# PCB-TLY-BRD-U.net
KiCad netlist of a schematic drawn in EAGLE
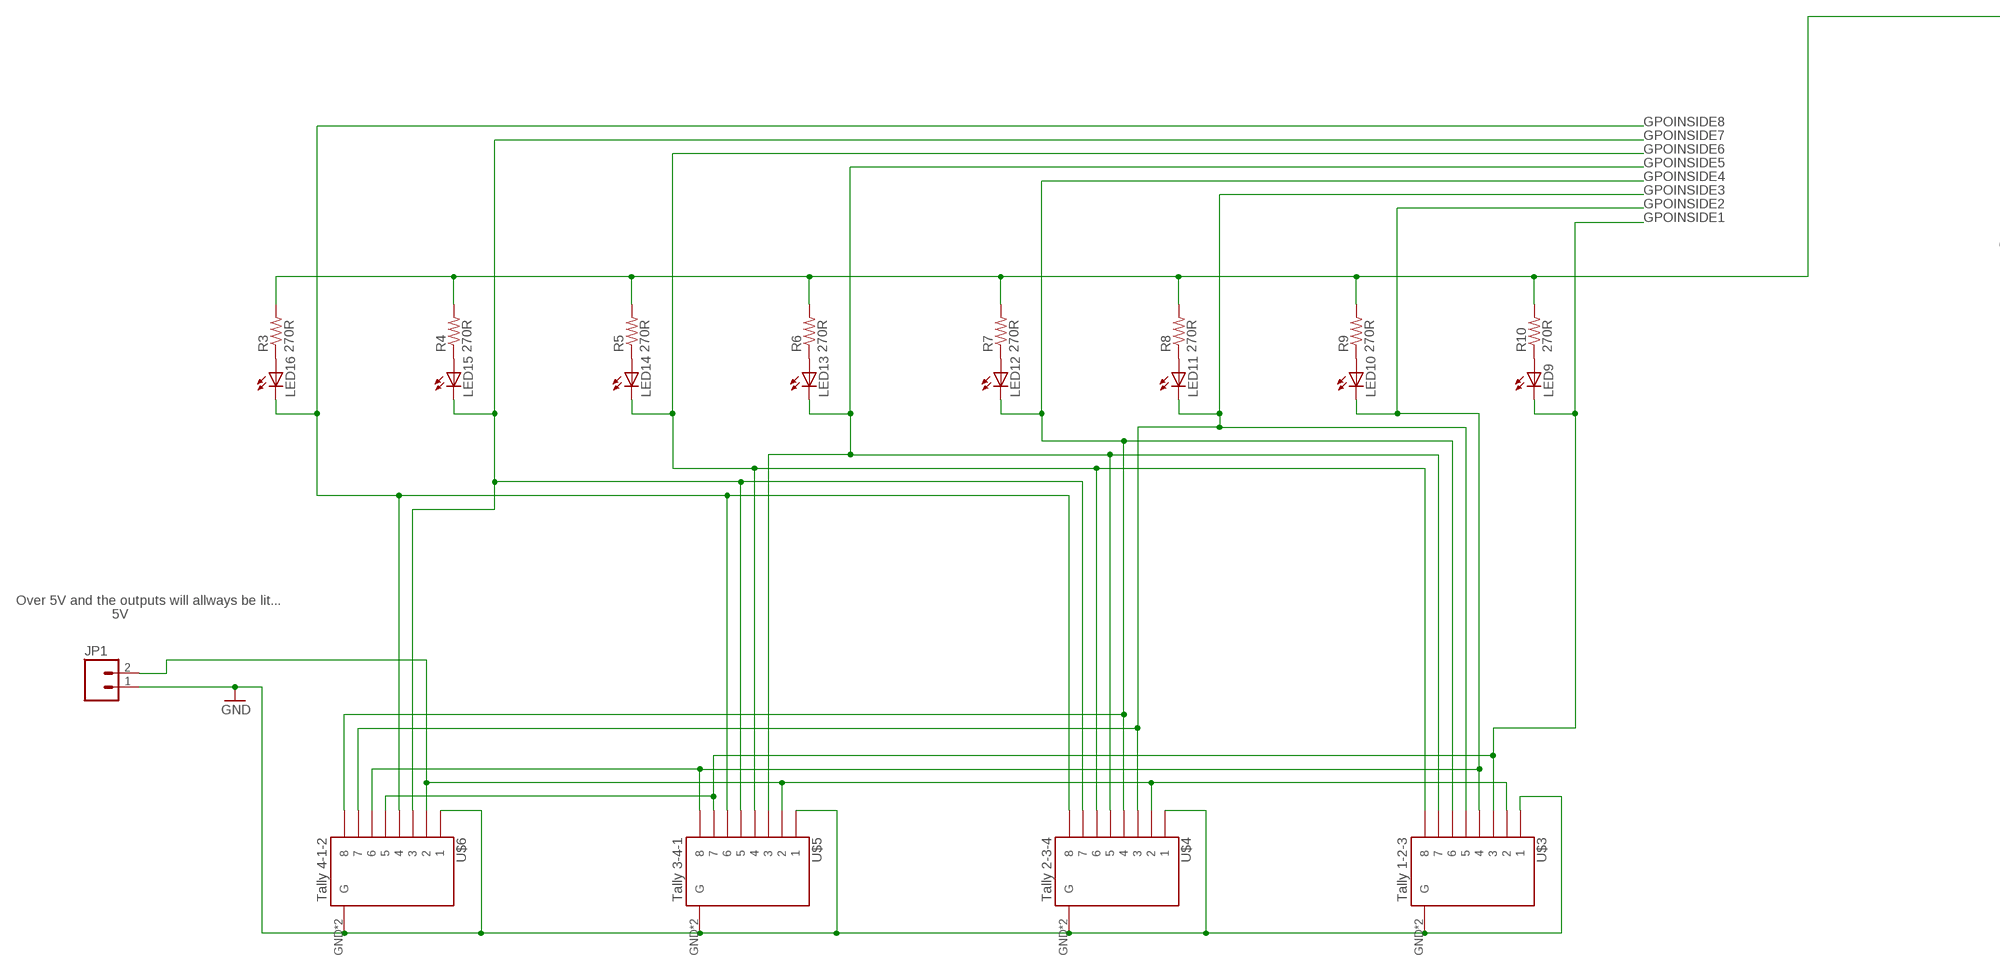
[diagram p0: schematic, sheet 1, part 1 of 2]
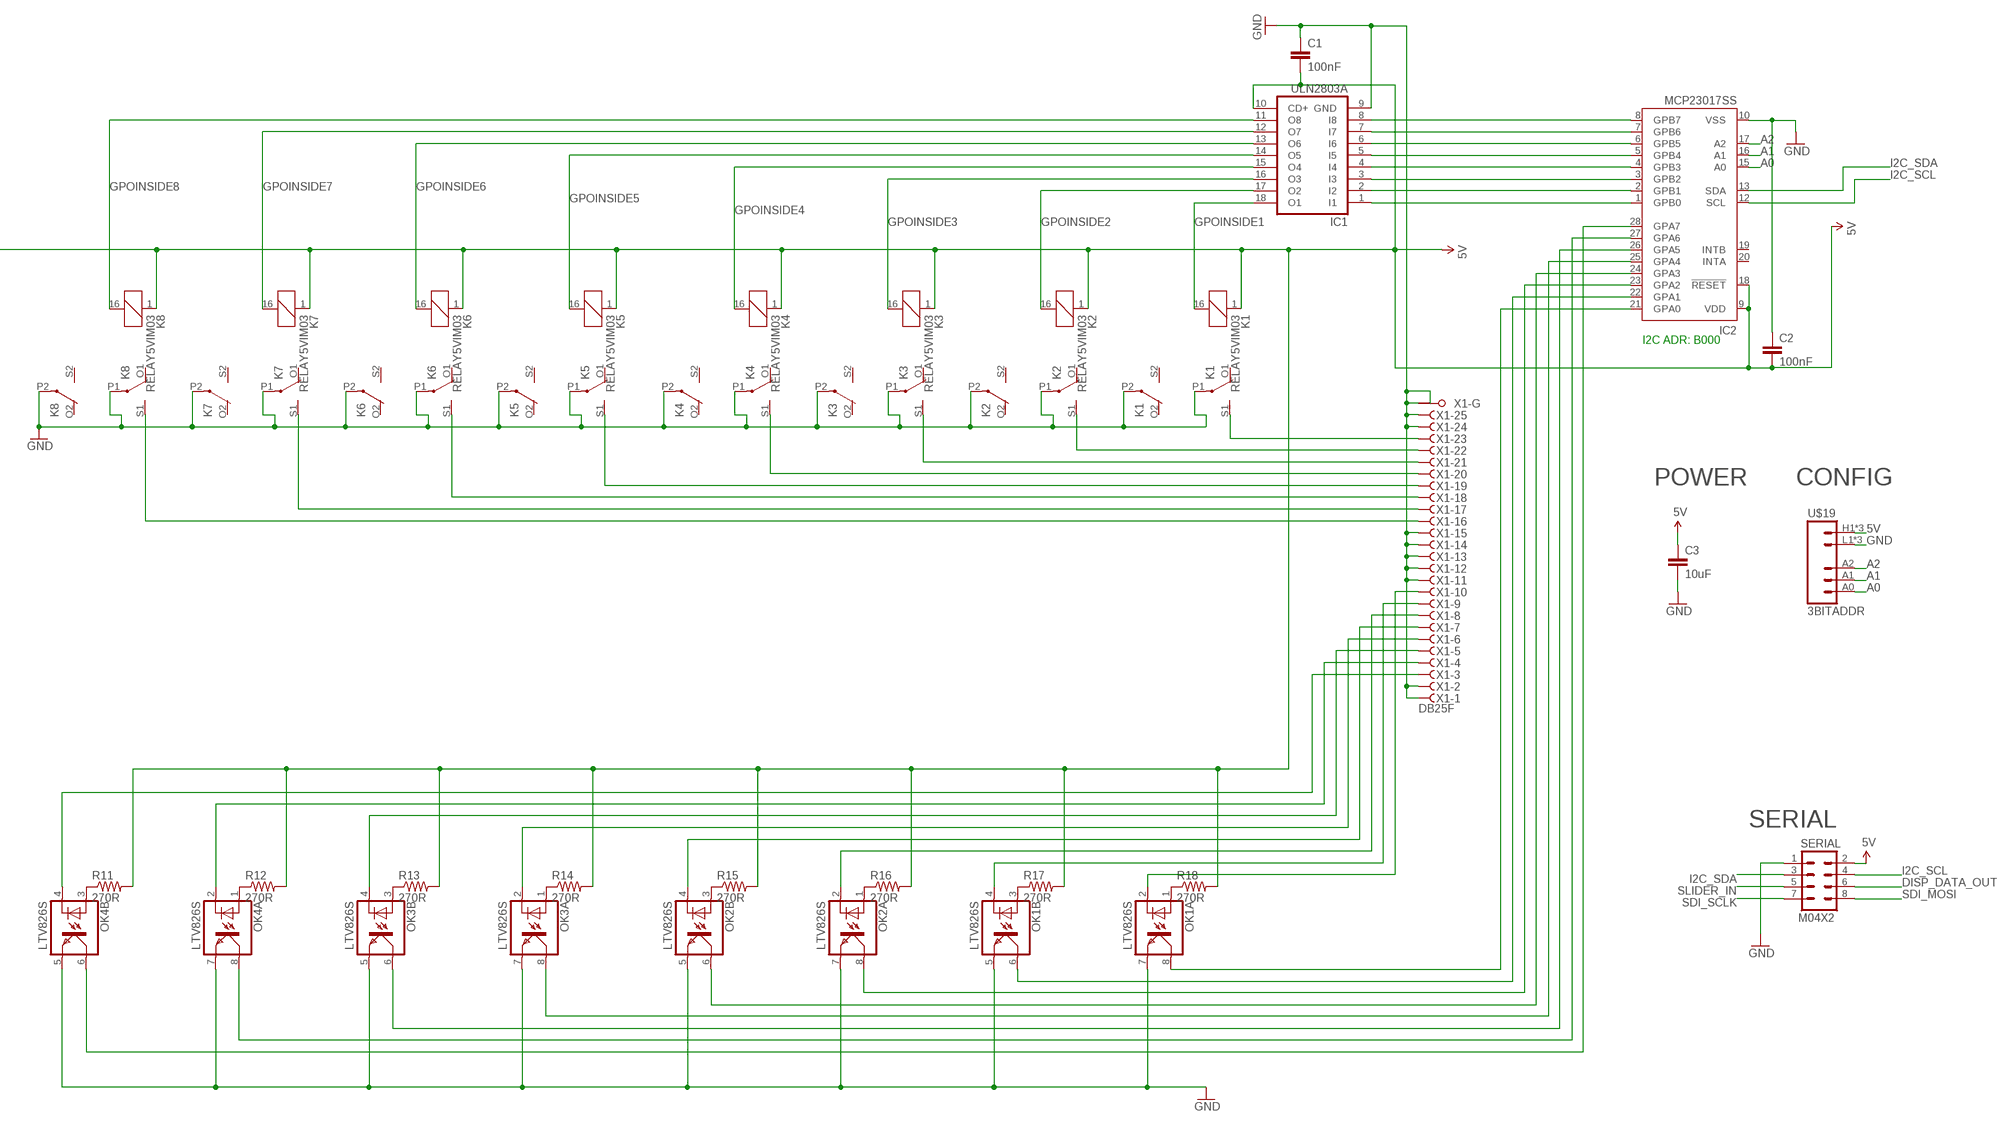
[diagram p1: schematic, sheet 1, part 2 of 2]

(export (version "E")
  (design (tool "Eeschema 10.0.6"))
  (components
    (comp (ref "C1")
      (value "100nF")
      (footprint "eagle-import:0805")
      (libsource (lib "eagle-import") (part "CAP0805"))
    )
    (comp (ref "C2")
      (value "100nF")
      (footprint "eagle-import:0603-CAP")
      (libsource (lib "eagle-import") (part "CAP0603-CAP"))
    )
    (comp (ref "C3")
      (value "10uF")
      (footprint "eagle-import:0805")
      (libsource (lib "eagle-import") (part "CAP0805"))
    )
    (comp (ref "IC1")
      (value "ULN2803A")
      (footprint "eagle-import:SO18W")
      (libsource (lib "eagle-import") (part "ULN2803ASO18W"))
    )
    (comp (ref "IC2")
      (value "MCP23017SS")
      (footprint "eagle-import:SSOP28")
      (fields (field (name "MF") "MICROCHIP") (field (name "MPN") "MCP23017-E/SS"))
      (libsource (lib "eagle-import") (part "MCP23017SS"))
    )
    (comp (ref "JP1")
      (value "M02PTH4")
      (footprint "eagle-import:1X02_XTRA_BIG")
      (libsource (lib "eagle-import") (part "M02PTH4"))
    )
    (comp (ref "K1")
      (value "RELAY5VIM03")
      (footprint "eagle-import:DS2Y")
      (libsource (lib "eagle-import") (part "RELAY5VIM03"))
    )
    (comp (ref "K2")
      (value "RELAY5VIM03")
      (footprint "eagle-import:DS2Y")
      (libsource (lib "eagle-import") (part "RELAY5VIM03"))
    )
    (comp (ref "K3")
      (value "RELAY5VIM03")
      (footprint "eagle-import:DS2Y")
      (libsource (lib "eagle-import") (part "RELAY5VIM03"))
    )
    (comp (ref "K4")
      (value "RELAY5VIM03")
      (footprint "eagle-import:DS2Y")
      (libsource (lib "eagle-import") (part "RELAY5VIM03"))
    )
    (comp (ref "K5")
      (value "RELAY5VIM03")
      (footprint "eagle-import:DS2Y")
      (libsource (lib "eagle-import") (part "RELAY5VIM03"))
    )
    (comp (ref "K6")
      (value "RELAY5VIM03")
      (footprint "eagle-import:DS2Y")
      (libsource (lib "eagle-import") (part "RELAY5VIM03"))
    )
    (comp (ref "K7")
      (value "RELAY5VIM03")
      (footprint "eagle-import:DS2Y")
      (libsource (lib "eagle-import") (part "RELAY5VIM03"))
    )
    (comp (ref "K8")
      (value "RELAY5VIM03")
      (footprint "eagle-import:DS2Y")
      (libsource (lib "eagle-import") (part "RELAY5VIM03"))
    )
    (comp (ref "LED9")
      (value "LED3MM")
      (footprint "eagle-import:LED3MM")
      (libsource (lib "eagle-import") (part "LED3MM"))
    )
    (comp (ref "LED10")
      (value "LED3MM")
      (footprint "eagle-import:LED3MM")
      (libsource (lib "eagle-import") (part "LED3MM"))
    )
    (comp (ref "LED11")
      (value "LED3MM")
      (footprint "eagle-import:LED3MM")
      (libsource (lib "eagle-import") (part "LED3MM"))
    )
    (comp (ref "LED12")
      (value "LED3MM")
      (footprint "eagle-import:LED3MM")
      (libsource (lib "eagle-import") (part "LED3MM"))
    )
    (comp (ref "LED13")
      (value "LED3MM")
      (footprint "eagle-import:LED3MM")
      (libsource (lib "eagle-import") (part "LED3MM"))
    )
    (comp (ref "LED14")
      (value "LED3MM")
      (footprint "eagle-import:LED3MM")
      (libsource (lib "eagle-import") (part "LED3MM"))
    )
    (comp (ref "LED15")
      (value "LED3MM")
      (footprint "eagle-import:LED3MM")
      (libsource (lib "eagle-import") (part "LED3MM"))
    )
    (comp (ref "LED16")
      (value "LED3MM")
      (footprint "eagle-import:LED3MM")
      (libsource (lib "eagle-import") (part "LED3MM"))
    )
    (comp (ref "OK1")
      (value "LTV826S")
      (footprint "eagle-import:DIL8-SMD")
      (libsource (lib "eagle-import") (part "LTV826S"))
    )
    (comp (ref "OK2")
      (value "LTV826S")
      (footprint "eagle-import:DIL8-SMD")
      (libsource (lib "eagle-import") (part "LTV826S"))
    )
    (comp (ref "OK3")
      (value "LTV826S")
      (footprint "eagle-import:DIL8-SMD")
      (libsource (lib "eagle-import") (part "LTV826S"))
    )
    (comp (ref "OK4")
      (value "LTV826S")
      (footprint "eagle-import:DIL8-SMD")
      (libsource (lib "eagle-import") (part "LTV826S"))
    )
    (comp (ref "R3")
      (value "270R")
      (footprint "eagle-import:0603-RES")
      (libsource (lib "eagle-import") (part "RESISTOR0603-RES"))
    )
    (comp (ref "R4")
      (value "270R")
      (footprint "eagle-import:0603-RES")
      (libsource (lib "eagle-import") (part "RESISTOR0603-RES"))
    )
    (comp (ref "R5")
      (value "270R")
      (footprint "eagle-import:0603-RES")
      (libsource (lib "eagle-import") (part "RESISTOR0603-RES"))
    )
    (comp (ref "R6")
      (value "270R")
      (footprint "eagle-import:0603-RES")
      (libsource (lib "eagle-import") (part "RESISTOR0603-RES"))
    )
    (comp (ref "R7")
      (value "270R")
      (footprint "eagle-import:0603-RES")
      (libsource (lib "eagle-import") (part "RESISTOR0603-RES"))
    )
    (comp (ref "R8")
      (value "270R")
      (footprint "eagle-import:0603-RES")
      (libsource (lib "eagle-import") (part "RESISTOR0603-RES"))
    )
    (comp (ref "R9")
      (value "270R")
      (footprint "eagle-import:0603-RES")
      (libsource (lib "eagle-import") (part "RESISTOR0603-RES"))
    )
    (comp (ref "R10")
      (value "270R")
      (footprint "eagle-import:0603-RES")
      (libsource (lib "eagle-import") (part "RESISTOR0603-RES"))
    )
    (comp (ref "R11")
      (value "270R")
      (footprint "eagle-import:0603-RES")
      (libsource (lib "eagle-import") (part "RESISTOR0603-RES"))
    )
    (comp (ref "R12")
      (value "270R")
      (footprint "eagle-import:0603-RES")
      (libsource (lib "eagle-import") (part "RESISTOR0603-RES"))
    )
    (comp (ref "R13")
      (value "270R")
      (footprint "eagle-import:0603-RES")
      (libsource (lib "eagle-import") (part "RESISTOR0603-RES"))
    )
    (comp (ref "R14")
      (value "270R")
      (footprint "eagle-import:0603-RES")
      (libsource (lib "eagle-import") (part "RESISTOR0603-RES"))
    )
    (comp (ref "R15")
      (value "270R")
      (footprint "eagle-import:0603-RES")
      (libsource (lib "eagle-import") (part "RESISTOR0603-RES"))
    )
    (comp (ref "R16")
      (value "270R")
      (footprint "eagle-import:0603-RES")
      (libsource (lib "eagle-import") (part "RESISTOR0603-RES"))
    )
    (comp (ref "R17")
      (value "270R")
      (footprint "eagle-import:0603-RES")
      (libsource (lib "eagle-import") (part "RESISTOR0603-RES"))
    )
    (comp (ref "R18")
      (value "270R")
      (footprint "eagle-import:0603-RES")
      (libsource (lib "eagle-import") (part "RESISTOR0603-RES"))
    )
    (comp (ref "SERIAL")
      (value "M04X2")
      (footprint "eagle-import:2X4")
      (libsource (lib "eagle-import") (part "M04X2"))
    )
    (comp (ref "U$3")
      (value "Tally 1-2-3")
      (footprint "eagle-import:RJ45-8_GND")
      (libsource (lib "eagle-import") (part "RJ45-8_GND"))
    )
    (comp (ref "U$4")
      (value "Tally 2-3-4")
      (footprint "eagle-import:RJ45-8_GND")
      (libsource (lib "eagle-import") (part "RJ45-8_GND"))
    )
    (comp (ref "U$5")
      (value "Tally 3-4-1")
      (footprint "eagle-import:RJ45-8_GND")
      (libsource (lib "eagle-import") (part "RJ45-8_GND"))
    )
    (comp (ref "U$6")
      (value "Tally 4-1-2")
      (footprint "eagle-import:RJ45-8_GND")
      (libsource (lib "eagle-import") (part "RJ45-8_GND"))
    )
    (comp (ref "U$19")
      (value "3BITADDR")
      (footprint "eagle-import:3BITADDR")
      (libsource (lib "eagle-import") (part "3BITADDR"))
    )
    (comp (ref "X1")
      (value "DB25F")
      (footprint "eagle-import:F25HP")
      (libsource (lib "eagle-import") (part "F25HPS"))
    )
  )
  (nets
    (net (code "1") (name "/A0") (class "Default")
      (node (ref "IC2") (pin "15") (pinfunction "A0_15") (pintype "input"))
      (node (ref "U$19") (pin "A0") (pinfunction "A0_A0") (pintype "passive"))
    )
    (net (code "2") (name "/A1") (class "Default")
      (node (ref "IC2") (pin "16") (pinfunction "A1_16") (pintype "input"))
      (node (ref "U$19") (pin "A1") (pinfunction "A1_A1") (pintype "passive"))
    )
    (net (code "3") (name "/A2") (class "Default")
      (node (ref "IC2") (pin "17") (pinfunction "A2_17") (pintype "input"))
      (node (ref "U$19") (pin "A2") (pinfunction "A2_A2") (pintype "passive"))
    )
    (net (code "4") (name "/DISP_DATA_OUT") (class "Default")
      (node (ref "SERIAL") (pin "6") (pinfunction "6_6") (pintype "passive"))
    )
    (net (code "5") (name "/GPOINSIDE1") (class "Default")
      (node (ref "IC1") (pin "18") (pinfunction "O1_18") (pintype "open_collector"))
      (node (ref "K1") (pin "16") (pinfunction "2_16") (pintype "passive"))
      (node (ref "LED9") (pin "K") (pinfunction "C_K") (pintype "passive"))
      (node (ref "U$3") (pin "3") (pinfunction "3_3") (pintype "bidirectional"))
      (node (ref "U$5") (pin "7") (pinfunction "7_7") (pintype "bidirectional"))
      (node (ref "U$6") (pin "5") (pinfunction "5_5") (pintype "bidirectional"))
    )
    (net (code "6") (name "/GPOINSIDE2") (class "Default")
      (node (ref "IC1") (pin "17") (pinfunction "O2_17") (pintype "open_collector"))
      (node (ref "K2") (pin "16") (pinfunction "2_16") (pintype "passive"))
      (node (ref "LED10") (pin "K") (pinfunction "C_K") (pintype "passive"))
      (node (ref "U$3") (pin "4") (pinfunction "4_4") (pintype "bidirectional"))
      (node (ref "U$5") (pin "8") (pinfunction "8_8") (pintype "bidirectional"))
      (node (ref "U$6") (pin "6") (pinfunction "6_6") (pintype "bidirectional"))
    )
    (net (code "7") (name "/GPOINSIDE3") (class "Default")
      (node (ref "IC1") (pin "16") (pinfunction "O3_16") (pintype "open_collector"))
      (node (ref "K3") (pin "16") (pinfunction "2_16") (pintype "passive"))
      (node (ref "LED11") (pin "K") (pinfunction "C_K") (pintype "passive"))
      (node (ref "U$3") (pin "5") (pinfunction "5_5") (pintype "bidirectional"))
      (node (ref "U$4") (pin "3") (pinfunction "3_3") (pintype "bidirectional"))
      (node (ref "U$6") (pin "7") (pinfunction "7_7") (pintype "bidirectional"))
    )
    (net (code "8") (name "/GPOINSIDE4") (class "Default")
      (node (ref "IC1") (pin "15") (pinfunction "O4_15") (pintype "open_collector"))
      (node (ref "K4") (pin "16") (pinfunction "2_16") (pintype "passive"))
      (node (ref "LED12") (pin "K") (pinfunction "C_K") (pintype "passive"))
      (node (ref "U$3") (pin "6") (pinfunction "6_6") (pintype "bidirectional"))
      (node (ref "U$4") (pin "4") (pinfunction "4_4") (pintype "bidirectional"))
      (node (ref "U$6") (pin "8") (pinfunction "8_8") (pintype "bidirectional"))
    )
    (net (code "9") (name "/GPOINSIDE5") (class "Default")
      (node (ref "IC1") (pin "14") (pinfunction "O5_14") (pintype "open_collector"))
      (node (ref "K5") (pin "16") (pinfunction "2_16") (pintype "passive"))
      (node (ref "LED13") (pin "K") (pinfunction "C_K") (pintype "passive"))
      (node (ref "U$3") (pin "7") (pinfunction "7_7") (pintype "bidirectional"))
      (node (ref "U$4") (pin "5") (pinfunction "5_5") (pintype "bidirectional"))
      (node (ref "U$5") (pin "3") (pinfunction "3_3") (pintype "bidirectional"))
    )
    (net (code "10") (name "/GPOINSIDE6") (class "Default")
      (node (ref "IC1") (pin "13") (pinfunction "O6_13") (pintype "open_collector"))
      (node (ref "K6") (pin "16") (pinfunction "2_16") (pintype "passive"))
      (node (ref "LED14") (pin "K") (pinfunction "C_K") (pintype "passive"))
      (node (ref "U$3") (pin "8") (pinfunction "8_8") (pintype "bidirectional"))
      (node (ref "U$4") (pin "6") (pinfunction "6_6") (pintype "bidirectional"))
      (node (ref "U$5") (pin "4") (pinfunction "4_4") (pintype "bidirectional"))
    )
    (net (code "11") (name "/GPOINSIDE7") (class "Default")
      (node (ref "IC1") (pin "12") (pinfunction "O7_12") (pintype "open_collector"))
      (node (ref "K7") (pin "16") (pinfunction "2_16") (pintype "passive"))
      (node (ref "LED15") (pin "K") (pinfunction "C_K") (pintype "passive"))
      (node (ref "U$4") (pin "7") (pinfunction "7_7") (pintype "bidirectional"))
      (node (ref "U$5") (pin "5") (pinfunction "5_5") (pintype "bidirectional"))
      (node (ref "U$6") (pin "3") (pinfunction "3_3") (pintype "bidirectional"))
    )
    (net (code "12") (name "/GPOINSIDE8") (class "Default")
      (node (ref "IC1") (pin "11") (pinfunction "O8_11") (pintype "open_collector"))
      (node (ref "K8") (pin "16") (pinfunction "2_16") (pintype "passive"))
      (node (ref "LED16") (pin "K") (pinfunction "C_K") (pintype "passive"))
      (node (ref "U$4") (pin "8") (pinfunction "8_8") (pintype "bidirectional"))
      (node (ref "U$5") (pin "6") (pinfunction "6_6") (pintype "bidirectional"))
      (node (ref "U$6") (pin "4") (pinfunction "4_4") (pintype "bidirectional"))
    )
    (net (code "13") (name "/I2C_SCL") (class "Default")
      (node (ref "IC2") (pin "12") (pinfunction "SCL_12") (pintype "input"))
      (node (ref "SERIAL") (pin "4") (pinfunction "4_4") (pintype "passive"))
    )
    (net (code "14") (name "/I2C_SDA") (class "Default")
      (node (ref "IC2") (pin "13") (pinfunction "SDA_13") (pintype "bidirectional"))
      (node (ref "SERIAL") (pin "3") (pinfunction "3_3") (pintype "passive"))
    )
    (net (code "15") (name "/SDI_MOSI") (class "Default")
      (node (ref "SERIAL") (pin "8") (pinfunction "8_8") (pintype "passive"))
    )
    (net (code "16") (name "/SDI_SCLK") (class "Default")
      (node (ref "SERIAL") (pin "7") (pinfunction "7_7") (pintype "passive"))
    )
    (net (code "17") (name "/SLIDER_IN") (class "Default")
      (node (ref "SERIAL") (pin "5") (pinfunction "5_5") (pintype "passive"))
    )
    (net (code "18") (name "5V") (class "Default")
      (node (ref "C1") (pin "2") (pinfunction "2_2") (pintype "passive"))
      (node (ref "C2") (pin "2") (pinfunction "2_2") (pintype "passive"))
      (node (ref "C3") (pin "1") (pinfunction "1_1") (pintype "passive"))
      (node (ref "IC1") (pin "10") (pinfunction "CD+_10") (pintype "passive"))
      (node (ref "IC2") (pin "18") (pinfunction "~{RESET}_18") (pintype "input"))
      (node (ref "IC2") (pin "9") (pinfunction "VDD_9") (pintype "power_in"))
      (node (ref "K1") (pin "1") (pinfunction "1_1") (pintype "passive"))
      (node (ref "K2") (pin "1") (pinfunction "1_1") (pintype "passive"))
      (node (ref "K3") (pin "1") (pinfunction "1_1") (pintype "passive"))
      (node (ref "K4") (pin "1") (pinfunction "1_1") (pintype "passive"))
      (node (ref "K5") (pin "1") (pinfunction "1_1") (pintype "passive"))
      (node (ref "K6") (pin "1") (pinfunction "1_1") (pintype "passive"))
      (node (ref "K7") (pin "1") (pinfunction "1_1") (pintype "passive"))
      (node (ref "K8") (pin "1") (pinfunction "1_1") (pintype "passive"))
      (node (ref "R10") (pin "2") (pinfunction "2_2") (pintype "passive"))
      (node (ref "R11") (pin "2") (pinfunction "2_2") (pintype "passive"))
      (node (ref "R12") (pin "2") (pinfunction "2_2") (pintype "passive"))
      (node (ref "R13") (pin "2") (pinfunction "2_2") (pintype "passive"))
      (node (ref "R14") (pin "2") (pinfunction "2_2") (pintype "passive"))
      (node (ref "R15") (pin "2") (pinfunction "2_2") (pintype "passive"))
      (node (ref "R16") (pin "2") (pinfunction "2_2") (pintype "passive"))
      (node (ref "R17") (pin "2") (pinfunction "2_2") (pintype "passive"))
      (node (ref "R18") (pin "2") (pinfunction "2_2") (pintype "passive"))
      (node (ref "R3") (pin "2") (pinfunction "2_2") (pintype "passive"))
      (node (ref "R4") (pin "2") (pinfunction "2_2") (pintype "passive"))
      (node (ref "R5") (pin "2") (pinfunction "2_2") (pintype "passive"))
      (node (ref "R6") (pin "2") (pinfunction "2_2") (pintype "passive"))
      (node (ref "R7") (pin "2") (pinfunction "2_2") (pintype "passive"))
      (node (ref "R8") (pin "2") (pinfunction "2_2") (pintype "passive"))
      (node (ref "R9") (pin "2") (pinfunction "2_2") (pintype "passive"))
      (node (ref "SERIAL") (pin "2") (pinfunction "2_2") (pintype "passive"))
      (node (ref "U$19") (pin "H1") (pinfunction "VCC_H1") (pintype "passive"))
      (node (ref "U$19") (pin "H2") (pinfunction "VCC_H2") (pintype "passive"))
      (node (ref "U$19") (pin "H3") (pinfunction "VCC_H3") (pintype "passive"))
    )
    (net (code "19") (name "GND") (class "Default")
      (node (ref "C1") (pin "1") (pinfunction "1_1") (pintype "passive"))
      (node (ref "C2") (pin "1") (pinfunction "1_1") (pintype "passive"))
      (node (ref "C3") (pin "2") (pinfunction "2_2") (pintype "passive"))
      (node (ref "IC1") (pin "9") (pinfunction "GND_9") (pintype "power_in"))
      (node (ref "IC2") (pin "10") (pinfunction "VSS_10") (pintype "power_in"))
      (node (ref "JP1") (pin "1") (pinfunction "1_1") (pintype "passive"))
      (node (ref "K1") (pin "P1") (pinfunction "P_P1") (pintype "passive"))
      (node (ref "K1") (pin "P2") (pinfunction "P_P2") (pintype "passive"))
      (node (ref "K2") (pin "P1") (pinfunction "P_P1") (pintype "passive"))
      (node (ref "K2") (pin "P2") (pinfunction "P_P2") (pintype "passive"))
      (node (ref "K3") (pin "P1") (pinfunction "P_P1") (pintype "passive"))
      (node (ref "K3") (pin "P2") (pinfunction "P_P2") (pintype "passive"))
      (node (ref "K4") (pin "P1") (pinfunction "P_P1") (pintype "passive"))
      (node (ref "K4") (pin "P2") (pinfunction "P_P2") (pintype "passive"))
      (node (ref "K5") (pin "P1") (pinfunction "P_P1") (pintype "passive"))
      (node (ref "K5") (pin "P2") (pinfunction "P_P2") (pintype "passive"))
      (node (ref "K6") (pin "P1") (pinfunction "P_P1") (pintype "passive"))
      (node (ref "K6") (pin "P2") (pinfunction "P_P2") (pintype "passive"))
      (node (ref "K7") (pin "P1") (pinfunction "P_P1") (pintype "passive"))
      (node (ref "K7") (pin "P2") (pinfunction "P_P2") (pintype "passive"))
      (node (ref "K8") (pin "P1") (pinfunction "P_P1") (pintype "passive"))
      (node (ref "K8") (pin "P2") (pinfunction "P_P2") (pintype "passive"))
      (node (ref "OK1") (pin "5") (pinfunction "EMIT_5") (pintype "passive"))
      (node (ref "OK1") (pin "7") (pinfunction "EMIT_7") (pintype "passive"))
      (node (ref "OK2") (pin "5") (pinfunction "EMIT_5") (pintype "passive"))
      (node (ref "OK2") (pin "7") (pinfunction "EMIT_7") (pintype "passive"))
      (node (ref "OK3") (pin "5") (pinfunction "EMIT_5") (pintype "passive"))
      (node (ref "OK3") (pin "7") (pinfunction "EMIT_7") (pintype "passive"))
      (node (ref "OK4") (pin "5") (pinfunction "EMIT_5") (pintype "passive"))
      (node (ref "OK4") (pin "7") (pinfunction "EMIT_7") (pintype "passive"))
      (node (ref "SERIAL") (pin "1") (pinfunction "1_1") (pintype "passive"))
      (node (ref "U$19") (pin "L1") (pinfunction "GND_L1") (pintype "passive"))
      (node (ref "U$19") (pin "L2") (pinfunction "GND_L2") (pintype "passive"))
      (node (ref "U$19") (pin "L3") (pinfunction "GND_L3") (pintype "passive"))
      (node (ref "U$3") (pin "1") (pinfunction "1_1") (pintype "bidirectional"))
      (node (ref "U$3") (pin "GND") (pinfunction "G_GND") (pintype "power_in"))
      (node (ref "U$3") (pin "GND1") (pinfunction "G_GND1") (pintype "power_in"))
      (node (ref "U$4") (pin "1") (pinfunction "1_1") (pintype "bidirectional"))
      (node (ref "U$4") (pin "GND") (pinfunction "G_GND") (pintype "power_in"))
      (node (ref "U$4") (pin "GND1") (pinfunction "G_GND1") (pintype "power_in"))
      (node (ref "U$5") (pin "1") (pinfunction "1_1") (pintype "bidirectional"))
      (node (ref "U$5") (pin "GND") (pinfunction "G_GND") (pintype "power_in"))
      (node (ref "U$5") (pin "GND1") (pinfunction "G_GND1") (pintype "power_in"))
      (node (ref "U$6") (pin "1") (pinfunction "1_1") (pintype "bidirectional"))
      (node (ref "U$6") (pin "GND") (pinfunction "G_GND") (pintype "power_in"))
      (node (ref "U$6") (pin "GND1") (pinfunction "G_GND1") (pintype "power_in"))
      (node (ref "X1") (pin "1") (pinfunction "F_1") (pintype "passive"))
      (node (ref "X1") (pin "11") (pinfunction "F_11") (pintype "passive"))
      (node (ref "X1") (pin "12") (pinfunction "F_12") (pintype "passive"))
      (node (ref "X1") (pin "13") (pinfunction "F_13") (pintype "passive"))
      (node (ref "X1") (pin "14") (pinfunction "F_14") (pintype "passive"))
      (node (ref "X1") (pin "15") (pinfunction "F_15") (pintype "passive"))
      (node (ref "X1") (pin "2") (pinfunction "F_2") (pintype "passive"))
      (node (ref "X1") (pin "24") (pinfunction "F_24") (pintype "passive"))
      (node (ref "X1") (pin "25") (pinfunction "F_25") (pintype "passive"))
      (node (ref "X1") (pin "G1") (pinfunction "G1_G1") (pintype "passive"))
      (node (ref "X1") (pin "G2") (pinfunction "G2_G2") (pintype "passive"))
    )
    (net (code "20") (name "Net-(IC1-I1)") (class "Default")
      (node (ref "IC1") (pin "1") (pinfunction "I1_1") (pintype "input"))
      (node (ref "IC2") (pin "1") (pinfunction "GPB0_1") (pintype "bidirectional"))
    )
    (net (code "21") (name "Net-(IC1-I2)") (class "Default")
      (node (ref "IC1") (pin "2") (pinfunction "I2_2") (pintype "input"))
      (node (ref "IC2") (pin "2") (pinfunction "GPB1_2") (pintype "bidirectional"))
    )
    (net (code "22") (name "Net-(IC1-I3)") (class "Default")
      (node (ref "IC1") (pin "3") (pinfunction "I3_3") (pintype "input"))
      (node (ref "IC2") (pin "3") (pinfunction "GPB2_3") (pintype "bidirectional"))
    )
    (net (code "23") (name "Net-(IC1-I4)") (class "Default")
      (node (ref "IC1") (pin "4") (pinfunction "I4_4") (pintype "input"))
      (node (ref "IC2") (pin "4") (pinfunction "GPB3_4") (pintype "bidirectional"))
    )
    (net (code "24") (name "Net-(IC1-I5)") (class "Default")
      (node (ref "IC1") (pin "5") (pinfunction "I5_5") (pintype "input"))
      (node (ref "IC2") (pin "5") (pinfunction "GPB4_5") (pintype "bidirectional"))
    )
    (net (code "25") (name "Net-(IC1-I6)") (class "Default")
      (node (ref "IC1") (pin "6") (pinfunction "I6_6") (pintype "input"))
      (node (ref "IC2") (pin "6") (pinfunction "GPB5_6") (pintype "bidirectional"))
    )
    (net (code "26") (name "Net-(IC1-I7)") (class "Default")
      (node (ref "IC1") (pin "7") (pinfunction "I7_7") (pintype "input"))
      (node (ref "IC2") (pin "7") (pinfunction "GPB6_7") (pintype "bidirectional"))
    )
    (net (code "27") (name "Net-(IC1-I8)") (class "Default")
      (node (ref "IC1") (pin "8") (pinfunction "I8_8") (pintype "input"))
      (node (ref "IC2") (pin "8") (pinfunction "GPB7_8") (pintype "bidirectional"))
    )
    (net (code "28") (name "Net-(IC2-GPA0)") (class "Default")
      (node (ref "IC2") (pin "21") (pinfunction "GPA0_21") (pintype "bidirectional"))
      (node (ref "OK1") (pin "8") (pinfunction "COL_8") (pintype "passive"))
    )
    (net (code "29") (name "Net-(IC2-GPA1)") (class "Default")
      (node (ref "IC2") (pin "22") (pinfunction "GPA1_22") (pintype "bidirectional"))
      (node (ref "OK1") (pin "6") (pinfunction "COL_6") (pintype "passive"))
    )
    (net (code "30") (name "Net-(IC2-GPA2)") (class "Default")
      (node (ref "IC2") (pin "23") (pinfunction "GPA2_23") (pintype "bidirectional"))
      (node (ref "OK2") (pin "8") (pinfunction "COL_8") (pintype "passive"))
    )
    (net (code "31") (name "Net-(IC2-GPA3)") (class "Default")
      (node (ref "IC2") (pin "24") (pinfunction "GPA3_24") (pintype "bidirectional"))
      (node (ref "OK2") (pin "6") (pinfunction "COL_6") (pintype "passive"))
    )
    (net (code "32") (name "Net-(IC2-GPA4)") (class "Default")
      (node (ref "IC2") (pin "25") (pinfunction "GPA4_25") (pintype "bidirectional"))
      (node (ref "OK3") (pin "8") (pinfunction "COL_8") (pintype "passive"))
    )
    (net (code "33") (name "Net-(IC2-GPA5)") (class "Default")
      (node (ref "IC2") (pin "26") (pinfunction "GPA5_26") (pintype "bidirectional"))
      (node (ref "OK3") (pin "6") (pinfunction "COL_6") (pintype "passive"))
    )
    (net (code "34") (name "Net-(IC2-GPA6)") (class "Default")
      (node (ref "IC2") (pin "27") (pinfunction "GPA6_27") (pintype "bidirectional"))
      (node (ref "OK4") (pin "8") (pinfunction "COL_8") (pintype "passive"))
    )
    (net (code "35") (name "Net-(IC2-GPA7)") (class "Default")
      (node (ref "IC2") (pin "28") (pinfunction "GPA7_28") (pintype "bidirectional"))
      (node (ref "OK4") (pin "6") (pinfunction "COL_6") (pintype "passive"))
    )
    (net (code "36") (name "Net-(JP1-Pad2)") (class "Default")
      (node (ref "JP1") (pin "2") (pinfunction "2_2") (pintype "passive"))
      (node (ref "U$3") (pin "2") (pinfunction "2_2") (pintype "bidirectional"))
      (node (ref "U$4") (pin "2") (pinfunction "2_2") (pintype "bidirectional"))
      (node (ref "U$5") (pin "2") (pinfunction "2_2") (pintype "bidirectional"))
      (node (ref "U$6") (pin "2") (pinfunction "2_2") (pintype "bidirectional"))
    )
    (net (code "37") (name "Net-(K1B-S)") (class "Default")
      (node (ref "K1") (pin "S1") (pinfunction "S_S1") (pintype "passive"))
      (node (ref "X1") (pin "23") (pinfunction "F_23") (pintype "passive"))
    )
    (net (code "38") (name "Net-(K2B-S)") (class "Default")
      (node (ref "K2") (pin "S1") (pinfunction "S_S1") (pintype "passive"))
      (node (ref "X1") (pin "22") (pinfunction "F_22") (pintype "passive"))
    )
    (net (code "39") (name "Net-(K3B-S)") (class "Default")
      (node (ref "K3") (pin "S1") (pinfunction "S_S1") (pintype "passive"))
      (node (ref "X1") (pin "21") (pinfunction "F_21") (pintype "passive"))
    )
    (net (code "40") (name "Net-(K4B-S)") (class "Default")
      (node (ref "K4") (pin "S1") (pinfunction "S_S1") (pintype "passive"))
      (node (ref "X1") (pin "20") (pinfunction "F_20") (pintype "passive"))
    )
    (net (code "41") (name "Net-(K5B-S)") (class "Default")
      (node (ref "K5") (pin "S1") (pinfunction "S_S1") (pintype "passive"))
      (node (ref "X1") (pin "19") (pinfunction "F_19") (pintype "passive"))
    )
    (net (code "42") (name "Net-(K6B-S)") (class "Default")
      (node (ref "K6") (pin "S1") (pinfunction "S_S1") (pintype "passive"))
      (node (ref "X1") (pin "18") (pinfunction "F_18") (pintype "passive"))
    )
    (net (code "43") (name "Net-(K7B-S)") (class "Default")
      (node (ref "K7") (pin "S1") (pinfunction "S_S1") (pintype "passive"))
      (node (ref "X1") (pin "17") (pinfunction "F_17") (pintype "passive"))
    )
    (net (code "44") (name "Net-(K8B-S)") (class "Default")
      (node (ref "K8") (pin "S1") (pinfunction "S_S1") (pintype "passive"))
      (node (ref "X1") (pin "16") (pinfunction "F_16") (pintype "passive"))
    )
    (net (code "45") (name "Net-(LED9-PadA)") (class "Default")
      (node (ref "LED9") (pin "A") (pinfunction "A_A") (pintype "passive"))
      (node (ref "R10") (pin "1") (pinfunction "1_1") (pintype "passive"))
    )
    (net (code "46") (name "Net-(LED10-PadA)") (class "Default")
      (node (ref "LED10") (pin "A") (pinfunction "A_A") (pintype "passive"))
      (node (ref "R9") (pin "1") (pinfunction "1_1") (pintype "passive"))
    )
    (net (code "47") (name "Net-(LED11-PadA)") (class "Default")
      (node (ref "LED11") (pin "A") (pinfunction "A_A") (pintype "passive"))
      (node (ref "R8") (pin "1") (pinfunction "1_1") (pintype "passive"))
    )
    (net (code "48") (name "Net-(LED12-PadA)") (class "Default")
      (node (ref "LED12") (pin "A") (pinfunction "A_A") (pintype "passive"))
      (node (ref "R7") (pin "1") (pinfunction "1_1") (pintype "passive"))
    )
    (net (code "49") (name "Net-(LED13-PadA)") (class "Default")
      (node (ref "LED13") (pin "A") (pinfunction "A_A") (pintype "passive"))
      (node (ref "R6") (pin "1") (pinfunction "1_1") (pintype "passive"))
    )
    (net (code "50") (name "Net-(LED14-PadA)") (class "Default")
      (node (ref "LED14") (pin "A") (pinfunction "A_A") (pintype "passive"))
      (node (ref "R5") (pin "1") (pinfunction "1_1") (pintype "passive"))
    )
    (net (code "51") (name "Net-(LED15-PadA)") (class "Default")
      (node (ref "LED15") (pin "A") (pinfunction "A_A") (pintype "passive"))
      (node (ref "R4") (pin "1") (pinfunction "1_1") (pintype "passive"))
    )
    (net (code "52") (name "Net-(LED16-PadA)") (class "Default")
      (node (ref "LED16") (pin "A") (pinfunction "A_A") (pintype "passive"))
      (node (ref "R3") (pin "1") (pinfunction "1_1") (pintype "passive"))
    )
    (net (code "53") (name "Net-(OK1A-A)") (class "Default")
      (node (ref "OK1") (pin "1") (pinfunction "A_1") (pintype "passive"))
      (node (ref "R18") (pin "1") (pinfunction "1_1") (pintype "passive"))
    )
    (net (code "54") (name "Net-(OK1A-C)") (class "Default")
      (node (ref "OK1") (pin "2") (pinfunction "C_2") (pintype "passive"))
      (node (ref "X1") (pin "10") (pinfunction "F_10") (pintype "passive"))
    )
    (net (code "55") (name "Net-(OK1B-A)") (class "Default")
      (node (ref "OK1") (pin "3") (pinfunction "A_3") (pintype "passive"))
      (node (ref "R17") (pin "1") (pinfunction "1_1") (pintype "passive"))
    )
    (net (code "56") (name "Net-(OK1B-C)") (class "Default")
      (node (ref "OK1") (pin "4") (pinfunction "C_4") (pintype "passive"))
      (node (ref "X1") (pin "9") (pinfunction "F_9") (pintype "passive"))
    )
    (net (code "57") (name "Net-(OK2A-A)") (class "Default")
      (node (ref "OK2") (pin "1") (pinfunction "A_1") (pintype "passive"))
      (node (ref "R16") (pin "1") (pinfunction "1_1") (pintype "passive"))
    )
    (net (code "58") (name "Net-(OK2A-C)") (class "Default")
      (node (ref "OK2") (pin "2") (pinfunction "C_2") (pintype "passive"))
      (node (ref "X1") (pin "8") (pinfunction "F_8") (pintype "passive"))
    )
    (net (code "59") (name "Net-(OK2B-A)") (class "Default")
      (node (ref "OK2") (pin "3") (pinfunction "A_3") (pintype "passive"))
      (node (ref "R15") (pin "1") (pinfunction "1_1") (pintype "passive"))
    )
    (net (code "60") (name "Net-(OK2B-C)") (class "Default")
      (node (ref "OK2") (pin "4") (pinfunction "C_4") (pintype "passive"))
      (node (ref "X1") (pin "7") (pinfunction "F_7") (pintype "passive"))
    )
    (net (code "61") (name "Net-(OK3A-A)") (class "Default")
      (node (ref "OK3") (pin "1") (pinfunction "A_1") (pintype "passive"))
      (node (ref "R14") (pin "1") (pinfunction "1_1") (pintype "passive"))
    )
    (net (code "62") (name "Net-(OK3A-C)") (class "Default")
      (node (ref "OK3") (pin "2") (pinfunction "C_2") (pintype "passive"))
      (node (ref "X1") (pin "6") (pinfunction "F_6") (pintype "passive"))
    )
    (net (code "63") (name "Net-(OK3B-A)") (class "Default")
      (node (ref "OK3") (pin "3") (pinfunction "A_3") (pintype "passive"))
      (node (ref "R13") (pin "1") (pinfunction "1_1") (pintype "passive"))
    )
    (net (code "64") (name "Net-(OK3B-C)") (class "Default")
      (node (ref "OK3") (pin "4") (pinfunction "C_4") (pintype "passive"))
      (node (ref "X1") (pin "5") (pinfunction "F_5") (pintype "passive"))
    )
    (net (code "65") (name "Net-(OK4A-A)") (class "Default")
      (node (ref "OK4") (pin "1") (pinfunction "A_1") (pintype "passive"))
      (node (ref "R12") (pin "1") (pinfunction "1_1") (pintype "passive"))
    )
    (net (code "66") (name "Net-(OK4A-C)") (class "Default")
      (node (ref "OK4") (pin "2") (pinfunction "C_2") (pintype "passive"))
      (node (ref "X1") (pin "4") (pinfunction "F_4") (pintype "passive"))
    )
    (net (code "67") (name "Net-(OK4B-A)") (class "Default")
      (node (ref "OK4") (pin "3") (pinfunction "A_3") (pintype "passive"))
      (node (ref "R11") (pin "1") (pinfunction "1_1") (pintype "passive"))
    )
    (net (code "68") (name "Net-(OK4B-C)") (class "Default")
      (node (ref "OK4") (pin "4") (pinfunction "C_4") (pintype "passive"))
      (node (ref "X1") (pin "3") (pinfunction "F_3") (pintype "passive"))
    )
    (net (code "69") (name "unconnected-(IC2-INTA-Pad20)") (class "Default")
      (node (ref "IC2") (pin "20") (pinfunction "INTA_20") (pintype "output"))
    )
    (net (code "70") (name "unconnected-(IC2-INTB-Pad19)") (class "Default")
      (node (ref "IC2") (pin "19") (pinfunction "INTB_19") (pintype "output"))
    )
    (net (code "71") (name "unconnected-(K1B-O-PadO1)") (class "Default")
      (node (ref "K1") (pin "O1") (pinfunction "O_O1") (pintype "passive"))
    )
    (net (code "72") (name "unconnected-(K1C-O-PadO2)") (class "Default")
      (node (ref "K1") (pin "O2") (pinfunction "O_O2") (pintype "passive"))
    )
    (net (code "73") (name "unconnected-(K1C-S-PadS2)") (class "Default")
      (node (ref "K1") (pin "S2") (pinfunction "S_S2") (pintype "passive"))
    )
    (net (code "74") (name "unconnected-(K2B-O-PadO1)") (class "Default")
      (node (ref "K2") (pin "O1") (pinfunction "O_O1") (pintype "passive"))
    )
    (net (code "75") (name "unconnected-(K2C-O-PadO2)") (class "Default")
      (node (ref "K2") (pin "O2") (pinfunction "O_O2") (pintype "passive"))
    )
    (net (code "76") (name "unconnected-(K2C-S-PadS2)") (class "Default")
      (node (ref "K2") (pin "S2") (pinfunction "S_S2") (pintype "passive"))
    )
    (net (code "77") (name "unconnected-(K3B-O-PadO1)") (class "Default")
      (node (ref "K3") (pin "O1") (pinfunction "O_O1") (pintype "passive"))
    )
    (net (code "78") (name "unconnected-(K3C-O-PadO2)") (class "Default")
      (node (ref "K3") (pin "O2") (pinfunction "O_O2") (pintype "passive"))
    )
    (net (code "79") (name "unconnected-(K3C-S-PadS2)") (class "Default")
      (node (ref "K3") (pin "S2") (pinfunction "S_S2") (pintype "passive"))
    )
    (net (code "80") (name "unconnected-(K4B-O-PadO1)") (class "Default")
      (node (ref "K4") (pin "O1") (pinfunction "O_O1") (pintype "passive"))
    )
    (net (code "81") (name "unconnected-(K4C-O-PadO2)") (class "Default")
      (node (ref "K4") (pin "O2") (pinfunction "O_O2") (pintype "passive"))
    )
    (net (code "82") (name "unconnected-(K4C-S-PadS2)") (class "Default")
      (node (ref "K4") (pin "S2") (pinfunction "S_S2") (pintype "passive"))
    )
    (net (code "83") (name "unconnected-(K5B-O-PadO1)") (class "Default")
      (node (ref "K5") (pin "O1") (pinfunction "O_O1") (pintype "passive"))
    )
    (net (code "84") (name "unconnected-(K5C-O-PadO2)") (class "Default")
      (node (ref "K5") (pin "O2") (pinfunction "O_O2") (pintype "passive"))
    )
    (net (code "85") (name "unconnected-(K5C-S-PadS2)") (class "Default")
      (node (ref "K5") (pin "S2") (pinfunction "S_S2") (pintype "passive"))
    )
    (net (code "86") (name "unconnected-(K6B-O-PadO1)") (class "Default")
      (node (ref "K6") (pin "O1") (pinfunction "O_O1") (pintype "passive"))
    )
    (net (code "87") (name "unconnected-(K6C-O-PadO2)") (class "Default")
      (node (ref "K6") (pin "O2") (pinfunction "O_O2") (pintype "passive"))
    )
    (net (code "88") (name "unconnected-(K6C-S-PadS2)") (class "Default")
      (node (ref "K6") (pin "S2") (pinfunction "S_S2") (pintype "passive"))
    )
    (net (code "89") (name "unconnected-(K7B-O-PadO1)") (class "Default")
      (node (ref "K7") (pin "O1") (pinfunction "O_O1") (pintype "passive"))
    )
    (net (code "90") (name "unconnected-(K7C-O-PadO2)") (class "Default")
      (node (ref "K7") (pin "O2") (pinfunction "O_O2") (pintype "passive"))
    )
    (net (code "91") (name "unconnected-(K7C-S-PadS2)") (class "Default")
      (node (ref "K7") (pin "S2") (pinfunction "S_S2") (pintype "passive"))
    )
    (net (code "92") (name "unconnected-(K8B-O-PadO1)") (class "Default")
      (node (ref "K8") (pin "O1") (pinfunction "O_O1") (pintype "passive"))
    )
    (net (code "93") (name "unconnected-(K8C-O-PadO2)") (class "Default")
      (node (ref "K8") (pin "O2") (pinfunction "O_O2") (pintype "passive"))
    )
    (net (code "94") (name "unconnected-(K8C-S-PadS2)") (class "Default")
      (node (ref "K8") (pin "S2") (pinfunction "S_S2") (pintype "passive"))
    )
  )
)
